# Sheet1.net
KiCad netlist of a schematic drawn in Altium Designer
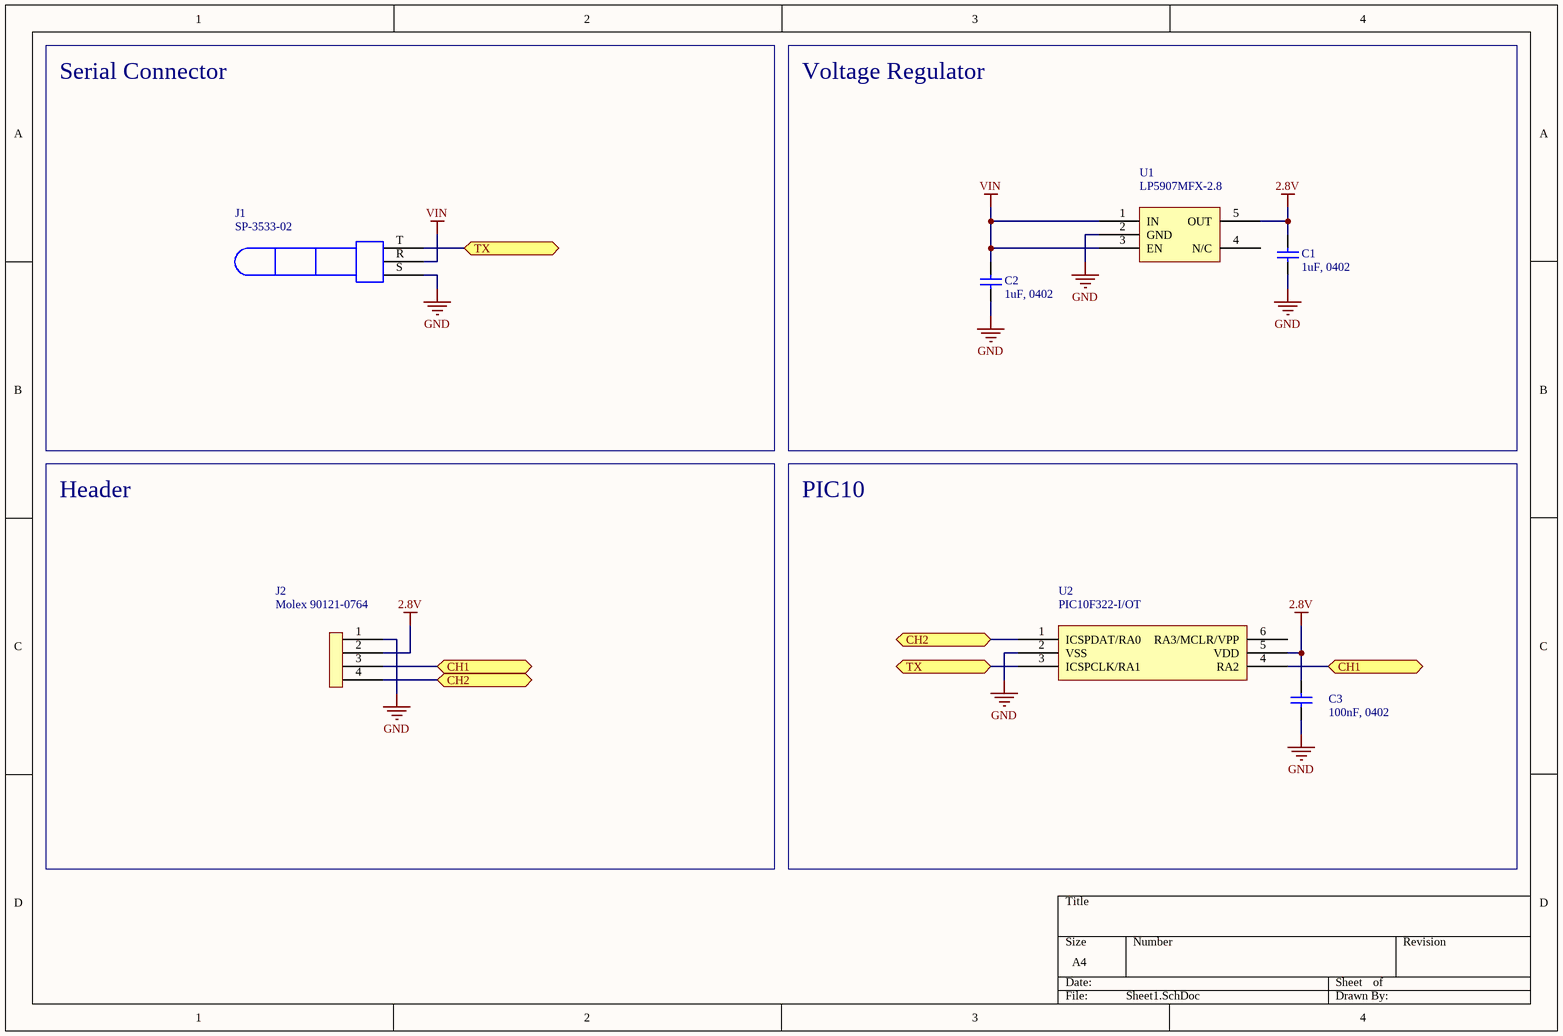
[diagram p0: Sheet1.SchDoc]

(export (version "E")
  (design (tool "Eeschema 10.0.6"))
  (components
    (comp (ref "C1")
      (value "1uF, 0402")
      (footprint "Capacitor 0402")
      (libsource (lib "x-io") (part "Capacitor"))
    )
    (comp (ref "C2")
      (value "1uF, 0402")
      (footprint "Capacitor 0402")
      (libsource (lib "x-io") (part "Capacitor"))
    )
    (comp (ref "C3")
      (value "100nF, 0402")
      (footprint "Capacitor 0402")
      (libsource (lib "x-io") (part "Capacitor"))
    )
    (comp (ref "J1")
      (value "SP-3533-02")
      (footprint "SP-3533-02")
      (libsource (lib "x-io") (part "SP-3533-02"))
    )
    (comp (ref "J2")
      (value "Molex 90121-0764")
      (footprint "Molex 90121-0764")
      (libsource (lib "x-io") (part "Molex 90121-0764"))
    )
    (comp (ref "U1")
      (value "LP5907MFX-2.8")
      (footprint "SOT-23-5")
      (libsource (lib "x-io") (part "LP5907MFX-X.X"))
    )
    (comp (ref "U2")
      (value "PIC10F322-I/OT")
      (footprint "SOT-23-6")
      (libsource (lib "x-io") (part "PIC10F322-I/OT"))
    )
  )
  (nets
    (net (code "1") (name "/CH1") (class "Default")
      (node (ref "J2") (pin "3") (pinfunction "3_3") (pintype "passive"))
      (node (ref "U2") (pin "4") (pinfunction "RA2_4") (pintype "passive"))
    )
    (net (code "2") (name "/CH2") (class "Default")
      (node (ref "J2") (pin "4") (pinfunction "4_4") (pintype "passive"))
      (node (ref "U2") (pin "1") (pinfunction "ICSPDAT/RA0_1") (pintype "passive"))
    )
    (net (code "3") (name "/TX") (class "Default")
      (node (ref "J1") (pin "T") (pinfunction "T_T") (pintype "passive"))
      (node (ref "U2") (pin "3") (pinfunction "ICSPCLK/RA1_3") (pintype "passive"))
    )
    (net (code "4") (name "2.8V") (class "Default")
      (node (ref "C1") (pin "2") (pinfunction "2_2") (pintype "passive"))
      (node (ref "C3") (pin "2") (pinfunction "2_2") (pintype "passive"))
      (node (ref "J2") (pin "2") (pinfunction "2_2") (pintype "passive"))
      (node (ref "U1") (pin "5") (pinfunction "OUT_5") (pintype "passive"))
      (node (ref "U2") (pin "5") (pinfunction "VDD_5") (pintype "passive"))
    )
    (net (code "5") (name "GND") (class "Default")
      (node (ref "C1") (pin "1") (pinfunction "1_1") (pintype "passive"))
      (node (ref "C2") (pin "1") (pinfunction "1_1") (pintype "passive"))
      (node (ref "C3") (pin "1") (pinfunction "1_1") (pintype "passive"))
      (node (ref "J1") (pin "S") (pinfunction "S_S") (pintype "passive"))
      (node (ref "J2") (pin "1") (pinfunction "1_1") (pintype "passive"))
      (node (ref "U1") (pin "2") (pinfunction "GND_2") (pintype "passive"))
      (node (ref "U2") (pin "2") (pinfunction "VSS_2") (pintype "passive"))
    )
    (net (code "6") (name "VIN") (class "Default")
      (node (ref "C2") (pin "2") (pinfunction "2_2") (pintype "passive"))
      (node (ref "J1") (pin "R") (pinfunction "R_R") (pintype "passive"))
      (node (ref "U1") (pin "1") (pinfunction "IN_1") (pintype "passive"))
      (node (ref "U1") (pin "3") (pinfunction "EN_3") (pintype "passive"))
    )
    (net (code "7") (name "unconnected-(U1-N{slash}C-Pad4)") (class "Default")
      (node (ref "U1") (pin "4") (pinfunction "N/C_4") (pintype "passive"))
    )
    (net (code "8") (name "unconnected-(U2-RA3{slash}MCLR{slash}VPP-Pad6)") (class "Default")
      (node (ref "U2") (pin "6") (pinfunction "RA3/MCLR/VPP_6") (pintype "passive"))
    )
  )
)
